# fmc_digital_io_ipmi.net
KiCad netlist of a schematic drawn in Altium Designer
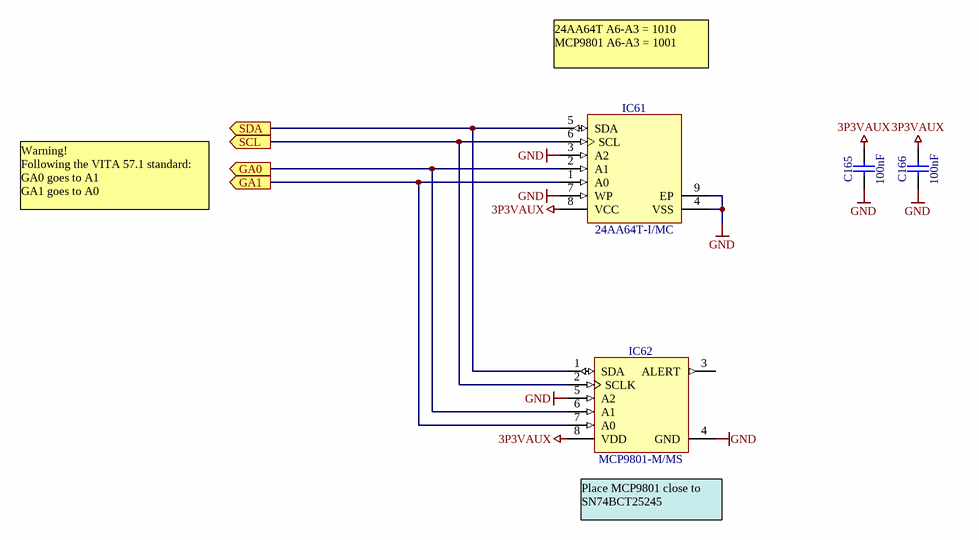
[diagram p0: fmc_digital_io_ipmi.SchDoc]

(export (version "E")
  (design (tool "Eeschema 10.0.6"))
  (components
    (comp (ref "C165")
      (value "100nF")
      (footprint "CAPC1005X55N")
      (description "Non-polarised capacitor")
      (fields
        (field (name "PART NUMBER") "CC0402_100NF_16V_10%_X5R")
        (field (name "VOLTAGE") "16V")
        (field (name "AUTHOR") "CERN DEM JLC")
      )
      (libsource (lib "Capacitors") (part "Capacitor - non polarized"))
    )
    (comp (ref "C166")
      (value "100nF")
      (footprint "CAPC1005X55N")
      (description "Non-polarised capacitor")
      (fields
        (field (name "PART NUMBER") "CC0402_100NF_16V_10%_X5R")
        (field (name "VOLTAGE") "16V")
        (field (name "AUTHOR") "CERN DEM JLC")
      )
      (libsource (lib "Capacitors") (part "Capacitor - non polarized"))
    )
    (comp (ref "IC61")
      (value "24AA64T-I/MC")
      (footprint "SON50P300X200X100-9N-S175X155")
      (description "1.7-5.5V 64K I2C Serial EEPROM")
      (fields (field (name "MANUFACTURER") "MICROCHIP TECHNOLOGY") (field (name "AUTHOR") "CERN DEM JLC"))
      (libsource (lib "ICs And Semiconductors") (part "24AA64T-I/MC"))
    )
    (comp (ref "IC62")
      (value "MCP9801-M/MS")
      (footprint "SOP65P490X110-8N")
      (description "2-Wire High-Accuracy Temperature Sensor")
      (fields (field (name "MANUFACTURER") "MICROCHIP TECHNOLOGIY") (field (name "AUTHOR") "CERN DEM JLC"))
      (libsource (lib "ICs And Semiconductors") (part "MCP9801-M/MS"))
    )
  )
  (nets
    (net (code "1") (name "/GA0") (class "Default")
      (node (ref "IC61") (pin "2") (pinfunction "A1_2") (pintype "input"))
      (node (ref "IC62") (pin "6") (pinfunction "A1_6") (pintype "input"))
    )
    (net (code "2") (name "/GA1") (class "Default")
      (node (ref "IC61") (pin "1") (pinfunction "A0_1") (pintype "input"))
      (node (ref "IC62") (pin "7") (pinfunction "A0_7") (pintype "input"))
    )
    (net (code "3") (name "/SCL") (class "Default")
      (node (ref "IC61") (pin "6") (pinfunction "SCL_6") (pintype "input"))
      (node (ref "IC62") (pin "2") (pinfunction "SCLK_2") (pintype "input"))
    )
    (net (code "4") (name "/SDA") (class "Default")
      (node (ref "IC61") (pin "5") (pinfunction "SDA_5") (pintype "bidirectional"))
      (node (ref "IC62") (pin "1") (pinfunction "SDA_1") (pintype "bidirectional"))
    )
    (net (code "5") (name "3P3VAUX") (class "Default")
      (node (ref "C165") (pin "2") (pinfunction "2_2") (pintype "passive"))
      (node (ref "C166") (pin "2") (pinfunction "2_2") (pintype "passive"))
      (node (ref "IC61") (pin "8") (pinfunction "VCC_8") (pintype "power_in"))
      (node (ref "IC62") (pin "8") (pinfunction "VDD_8") (pintype "power_in"))
    )
    (net (code "6") (name "GND") (class "Default")
      (node (ref "C165") (pin "1") (pinfunction "1_1") (pintype "passive"))
      (node (ref "C166") (pin "1") (pinfunction "1_1") (pintype "passive"))
      (node (ref "IC61") (pin "3") (pinfunction "A2_3") (pintype "input"))
      (node (ref "IC61") (pin "4") (pinfunction "VSS_4") (pintype "power_in"))
      (node (ref "IC61") (pin "7") (pinfunction "WP_7") (pintype "input"))
      (node (ref "IC61") (pin "9") (pinfunction "EP_9") (pintype "power_in"))
      (node (ref "IC62") (pin "4") (pinfunction "GND_4") (pintype "power_in"))
      (node (ref "IC62") (pin "5") (pinfunction "A2_5") (pintype "input"))
    )
    (net (code "7") (name "unconnected-(IC62-ALERT-Pad3)") (class "Default")
      (node (ref "IC62") (pin "3") (pinfunction "ALERT_3") (pintype "output"))
    )
  )
)
